# PT100.net
KiCad netlist of a schematic drawn in Altium Designer
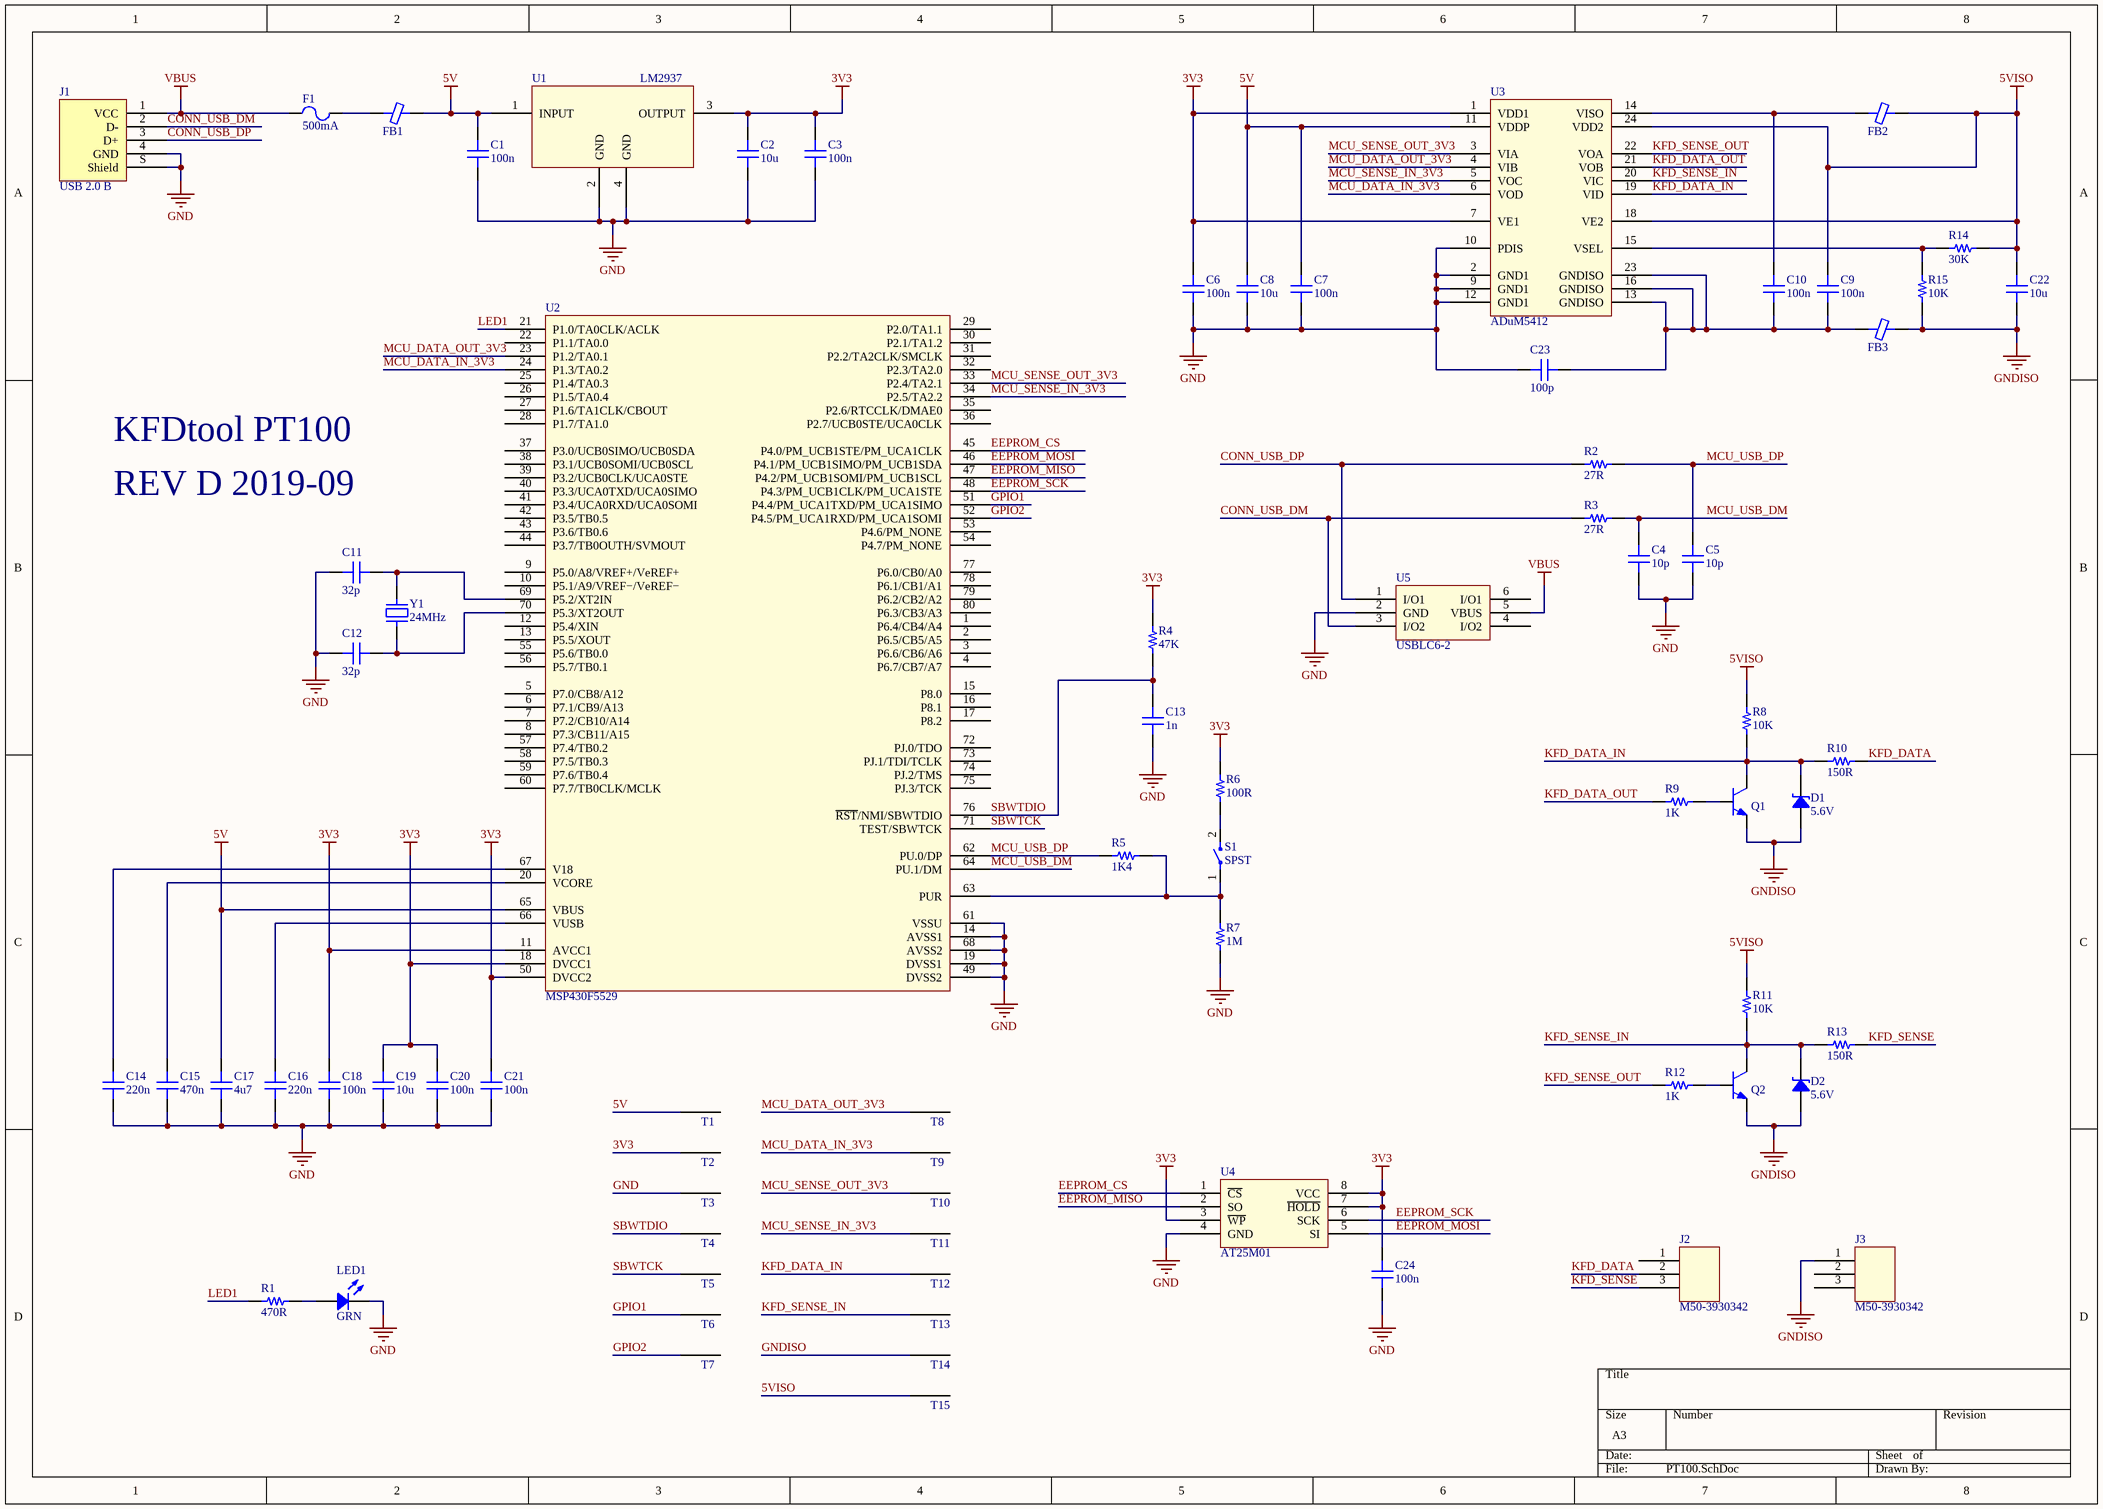
[diagram p0: PT100.SchDoc]

(export (version "E")
  (design (tool "Eeschema 10.0.6"))
  (components
    (comp (ref "C1")
      (value "100n")
      (footprint "CAP 0603")
      (libsource (lib "KFDtool Schematic Library") (part "Capacitor"))
    )
    (comp (ref "C2")
      (value "10u")
      (footprint "CAP 0603")
      (libsource (lib "KFDtool Schematic Library") (part "Capacitor"))
    )
    (comp (ref "C3")
      (value "100n")
      (footprint "CAP 0603")
      (libsource (lib "KFDtool Schematic Library") (part "Capacitor"))
    )
    (comp (ref "C4")
      (value "10p")
      (footprint "CAP 0603")
      (libsource (lib "KFDtool Schematic Library") (part "Capacitor"))
    )
    (comp (ref "C5")
      (value "10p")
      (footprint "CAP 0603")
      (libsource (lib "KFDtool Schematic Library") (part "Capacitor"))
    )
    (comp (ref "C6")
      (value "100n")
      (footprint "CAP 0603")
      (libsource (lib "KFDtool Schematic Library") (part "Capacitor"))
    )
    (comp (ref "C7")
      (value "100n")
      (footprint "CAP 0603")
      (libsource (lib "KFDtool Schematic Library") (part "Capacitor"))
    )
    (comp (ref "C8")
      (value "10u")
      (footprint "CAP 0603")
      (libsource (lib "KFDtool Schematic Library") (part "Capacitor"))
    )
    (comp (ref "C9")
      (value "100n")
      (footprint "CAP 0603")
      (libsource (lib "KFDtool Schematic Library") (part "Capacitor"))
    )
    (comp (ref "C10")
      (value "100n")
      (footprint "CAP 0603")
      (libsource (lib "KFDtool Schematic Library") (part "Capacitor"))
    )
    (comp (ref "C11")
      (value "32p")
      (footprint "CAP 0603")
      (libsource (lib "KFDtool Schematic Library") (part "Capacitor"))
    )
    (comp (ref "C12")
      (value "32p")
      (footprint "CAP 0603")
      (libsource (lib "KFDtool Schematic Library") (part "Capacitor"))
    )
    (comp (ref "C13")
      (value "1n")
      (footprint "CAP 0603")
      (libsource (lib "KFDtool Schematic Library") (part "Capacitor"))
    )
    (comp (ref "C14")
      (value "220n")
      (footprint "CAP 0603")
      (libsource (lib "KFDtool Schematic Library") (part "Capacitor"))
    )
    (comp (ref "C15")
      (value "470n")
      (footprint "CAP 0603")
      (libsource (lib "KFDtool Schematic Library") (part "Capacitor"))
    )
    (comp (ref "C16")
      (value "220n")
      (footprint "CAP 0603")
      (libsource (lib "KFDtool Schematic Library") (part "Capacitor"))
    )
    (comp (ref "C17")
      (value "4u7")
      (footprint "CAP 0603")
      (libsource (lib "KFDtool Schematic Library") (part "Capacitor"))
    )
    (comp (ref "C18")
      (value "100n")
      (footprint "CAP 0603")
      (libsource (lib "KFDtool Schematic Library") (part "Capacitor"))
    )
    (comp (ref "C19")
      (value "10u")
      (footprint "CAP 0603")
      (libsource (lib "KFDtool Schematic Library") (part "Capacitor"))
    )
    (comp (ref "C20")
      (value "100n")
      (footprint "CAP 0603")
      (libsource (lib "KFDtool Schematic Library") (part "Capacitor"))
    )
    (comp (ref "C21")
      (value "100n")
      (footprint "CAP 0603")
      (libsource (lib "KFDtool Schematic Library") (part "Capacitor"))
    )
    (comp (ref "C22")
      (value "10u")
      (footprint "CAP 0603")
      (libsource (lib "KFDtool Schematic Library") (part "Capacitor"))
    )
    (comp (ref "C23")
      (value "100p")
      (footprint "CAP 1812")
      (libsource (lib "KFDtool Schematic Library") (part "Capacitor"))
    )
    (comp (ref "C24")
      (value "100n")
      (footprint "CAP 0603")
      (libsource (lib "KFDtool Schematic Library") (part "Capacitor"))
    )
    (comp (ref "D1")
      (value "5.6V")
      (footprint "ON SEMI SOT-23-3")
      (libsource (lib "KFDtool Schematic Library") (part "Zener Diode"))
    )
    (comp (ref "D2")
      (value "5.6V")
      (footprint "ON SEMI SOT-23-3")
      (libsource (lib "KFDtool Schematic Library") (part "Zener Diode"))
    )
    (comp (ref "F1")
      (value "500mA")
      (footprint "PTC 2920")
      (libsource (lib "KFDtool Schematic Library") (part "PTC"))
    )
    (comp (ref "FB1")
      (value "Ferrite Chip")
      (footprint "CAP 0603")
      (libsource (lib "KFDtool Schematic Library") (part "Ferrite Chip"))
    )
    (comp (ref "FB2")
      (value "Ferrite Chip")
      (footprint "CAP 0603")
      (libsource (lib "KFDtool Schematic Library") (part "Ferrite Chip"))
    )
    (comp (ref "FB3")
      (value "Ferrite Chip")
      (footprint "CAP 0603")
      (libsource (lib "KFDtool Schematic Library") (part "Ferrite Chip"))
    )
    (comp (ref "J1")
      (value "USB 2.0 B")
      (footprint "FCI 61729-1011BLF")
      (libsource (lib "KFDtool Schematic Library") (part "FCI 61729-1011BLF"))
    )
    (comp (ref "J2")
      (value "M50-3930342")
      (footprint "HWN M50-3930342")
      (libsource (lib "KFDtool Schematic Library") (part "HWN M50-3930342"))
    )
    (comp (ref "J3")
      (value "M50-3930342")
      (footprint "HWN M50-3930342")
      (libsource (lib "KFDtool Schematic Library") (part "HWN M50-3930342"))
    )
    (comp (ref "LED1")
      (value "GRN")
      (footprint "KBRT WP934CB/GD")
      (libsource (lib "KFDtool Schematic Library") (part "LED"))
    )
    (comp (ref "Q1")
      (value "NPN Transistor")
      (footprint "ON SEMI SOT-23-3")
      (libsource (lib "KFDtool Schematic Library") (part "NPN Transistor"))
    )
    (comp (ref "Q2")
      (value "NPN Transistor")
      (footprint "ON SEMI SOT-23-3")
      (libsource (lib "KFDtool Schematic Library") (part "NPN Transistor"))
    )
    (comp (ref "R1")
      (value "470R")
      (footprint "RES 0603")
      (libsource (lib "KFDtool Schematic Library") (part "Resistor"))
    )
    (comp (ref "R2")
      (value "27R")
      (footprint "RES 0603")
      (libsource (lib "KFDtool Schematic Library") (part "Resistor"))
    )
    (comp (ref "R3")
      (value "27R")
      (footprint "RES 0603")
      (libsource (lib "KFDtool Schematic Library") (part "Resistor"))
    )
    (comp (ref "R4")
      (value "47K")
      (footprint "RES 0603")
      (libsource (lib "KFDtool Schematic Library") (part "Resistor"))
    )
    (comp (ref "R5")
      (value "1K4")
      (footprint "RES 0603")
      (libsource (lib "KFDtool Schematic Library") (part "Resistor"))
    )
    (comp (ref "R6")
      (value "100R")
      (footprint "RES 0603")
      (libsource (lib "KFDtool Schematic Library") (part "Resistor"))
    )
    (comp (ref "R7")
      (value "1M")
      (footprint "RES 0603")
      (libsource (lib "KFDtool Schematic Library") (part "Resistor"))
    )
    (comp (ref "R8")
      (value "10K")
      (footprint "RES 0603")
      (libsource (lib "KFDtool Schematic Library") (part "Resistor"))
    )
    (comp (ref "R9")
      (value "1K")
      (footprint "RES 0603")
      (libsource (lib "KFDtool Schematic Library") (part "Resistor"))
    )
    (comp (ref "R10")
      (value "150R")
      (footprint "RES 0603")
      (libsource (lib "KFDtool Schematic Library") (part "Resistor"))
    )
    (comp (ref "R11")
      (value "10K")
      (footprint "RES 0603")
      (libsource (lib "KFDtool Schematic Library") (part "Resistor"))
    )
    (comp (ref "R12")
      (value "1K")
      (footprint "RES 0603")
      (libsource (lib "KFDtool Schematic Library") (part "Resistor"))
    )
    (comp (ref "R13")
      (value "150R")
      (footprint "RES 0603")
      (libsource (lib "KFDtool Schematic Library") (part "Resistor"))
    )
    (comp (ref "R14")
      (value "30K")
      (footprint "RES 0603")
      (libsource (lib "KFDtool Schematic Library") (part "Resistor"))
    )
    (comp (ref "R15")
      (value "10K")
      (footprint "RES 0603")
      (libsource (lib "KFDtool Schematic Library") (part "Resistor"))
    )
    (comp (ref "S1")
      (value "SPST")
      (footprint "ESWI TL3340AF160QG")
      (libsource (lib "KFDtool Schematic Library") (part "SPST Switch"))
    )
    (comp (ref "T1")
      (value "Test Point")
      (footprint "TEST POINT")
      (libsource (lib "KFDtool Schematic Library") (part "Test Point"))
    )
    (comp (ref "T2")
      (value "Test Point")
      (footprint "TEST POINT")
      (libsource (lib "KFDtool Schematic Library") (part "Test Point"))
    )
    (comp (ref "T3")
      (value "Test Point")
      (footprint "TEST POINT")
      (libsource (lib "KFDtool Schematic Library") (part "Test Point"))
    )
    (comp (ref "T4")
      (value "Test Point")
      (footprint "TEST POINT")
      (libsource (lib "KFDtool Schematic Library") (part "Test Point"))
    )
    (comp (ref "T5")
      (value "Test Point")
      (footprint "TEST POINT")
      (libsource (lib "KFDtool Schematic Library") (part "Test Point"))
    )
    (comp (ref "T6")
      (value "Test Point")
      (footprint "TEST POINT")
      (libsource (lib "KFDtool Schematic Library") (part "Test Point"))
    )
    (comp (ref "T7")
      (value "Test Point")
      (footprint "TEST POINT")
      (libsource (lib "KFDtool Schematic Library") (part "Test Point"))
    )
    (comp (ref "T8")
      (value "Test Point")
      (footprint "TEST POINT")
      (libsource (lib "KFDtool Schematic Library") (part "Test Point"))
    )
    (comp (ref "T9")
      (value "Test Point")
      (footprint "TEST POINT")
      (libsource (lib "KFDtool Schematic Library") (part "Test Point"))
    )
    (comp (ref "T10")
      (value "Test Point")
      (footprint "TEST POINT")
      (libsource (lib "KFDtool Schematic Library") (part "Test Point"))
    )
    (comp (ref "T11")
      (value "Test Point")
      (footprint "TEST POINT")
      (libsource (lib "KFDtool Schematic Library") (part "Test Point"))
    )
    (comp (ref "T12")
      (value "Test Point")
      (footprint "TEST POINT")
      (libsource (lib "KFDtool Schematic Library") (part "Test Point"))
    )
    (comp (ref "T13")
      (value "Test Point")
      (footprint "TEST POINT")
      (libsource (lib "KFDtool Schematic Library") (part "Test Point"))
    )
    (comp (ref "T14")
      (value "Test Point")
      (footprint "TEST POINT")
      (libsource (lib "KFDtool Schematic Library") (part "Test Point"))
    )
    (comp (ref "T15")
      (value "Test Point")
      (footprint "TEST POINT")
      (libsource (lib "KFDtool Schematic Library") (part "Test Point"))
    )
    (comp (ref "U1")
      (value "LM2937")
      (footprint "TI LM2937IMP-3.3/NOPB")
      (libsource (lib "KFDtool Schematic Library") (part "TI LM2937"))
    )
    (comp (ref "U2")
      (value "MSP430F5529")
      (footprint "TI MSP430F5529IPNR")
      (libsource (lib "KFDtool Schematic Library") (part "TI MSP430F5529"))
    )
    (comp (ref "U3")
      (value "ADuM5412")
      (footprint "AD RS-24")
      (libsource (lib "KFDtool Schematic Library") (part "AD ADuM5412"))
    )
    (comp (ref "U4")
      (value "AT25M01")
      (footprint "ATML 8S1")
      (libsource (lib "KFDtool Schematic Library") (part "ATML AT25M01"))
    )
    (comp (ref "U5")
      (value "USBLC6-2")
      (footprint "ST SOT23-6L")
      (libsource (lib "KFDtool Schematic Library") (part "ST USBLC6-2"))
    )
    (comp (ref "Y1")
      (value "24MHz")
      (footprint "ABRA ABLS2")
      (libsource (lib "KFDtool Schematic Library") (part "Crystal"))
    )
  )
  (nets
    (net (code "1") (name "/CONN_USB_DM") (class "Default")
      (node (ref "J1") (pin "2") (pinfunction "D-_2") (pintype "passive"))
      (node (ref "R3") (pin "1") (pinfunction "1_1") (pintype "passive"))
      (node (ref "U5") (pin "3") (pinfunction "I/O2_3") (pintype "passive"))
    )
    (net (code "2") (name "/CONN_USB_DP") (class "Default")
      (node (ref "J1") (pin "3") (pinfunction "D+_3") (pintype "passive"))
      (node (ref "R2") (pin "1") (pinfunction "1_1") (pintype "passive"))
      (node (ref "U5") (pin "1") (pinfunction "I/O1_1") (pintype "passive"))
    )
    (net (code "3") (name "/EEPROM_CS") (class "Default")
      (node (ref "U2") (pin "45") (pinfunction "P4.0/PM_UCB1STE/PM_UCA1CLK_45") (pintype "passive"))
      (node (ref "U4") (pin "1") (pinfunction "~{CS}_1") (pintype "passive"))
    )
    (net (code "4") (name "/EEPROM_MISO") (class "Default")
      (node (ref "U2") (pin "47") (pinfunction "P4.2/PM_UCB1SOMI/PM_UCB1SCL_47") (pintype "passive"))
      (node (ref "U4") (pin "2") (pinfunction "SO_2") (pintype "passive"))
    )
    (net (code "5") (name "/EEPROM_MOSI") (class "Default")
      (node (ref "U2") (pin "46") (pinfunction "P4.1/PM_UCB1SIMO/PM_UCB1SDA_46") (pintype "passive"))
      (node (ref "U4") (pin "5") (pinfunction "SI_5") (pintype "passive"))
    )
    (net (code "6") (name "/EEPROM_SCK") (class "Default")
      (node (ref "U2") (pin "48") (pinfunction "P4.3/PM_UCB1CLK/PM_UCA1STE_48") (pintype "passive"))
      (node (ref "U4") (pin "6") (pinfunction "SCK_6") (pintype "passive"))
    )
    (net (code "7") (name "/GPIO1") (class "Default")
      (node (ref "T6") (pin "1") (pinfunction "1_1") (pintype "passive"))
      (node (ref "U2") (pin "51") (pinfunction "P4.4/PM_UCA1TXD/PM_UCA1SIMO_51") (pintype "passive"))
    )
    (net (code "8") (name "/GPIO2") (class "Default")
      (node (ref "T7") (pin "1") (pinfunction "1_1") (pintype "passive"))
      (node (ref "U2") (pin "52") (pinfunction "P4.5/PM_UCA1RXD/PM_UCA1SOMI_52") (pintype "passive"))
    )
    (net (code "9") (name "/KFD_DATA") (class "Default")
      (node (ref "J2") (pin "2") (pinfunction "2_2") (pintype "passive"))
      (node (ref "R10") (pin "2") (pinfunction "2_2") (pintype "passive"))
    )
    (net (code "10") (name "/KFD_DATA_IN") (class "Default")
      (node (ref "D1") (pin "C") (pinfunction "C_C") (pintype "passive"))
      (node (ref "Q1") (pin "C") (pinfunction "C_C") (pintype "passive"))
      (node (ref "R10") (pin "1") (pinfunction "1_1") (pintype "passive"))
      (node (ref "R8") (pin "1") (pinfunction "1_1") (pintype "passive"))
      (node (ref "T12") (pin "1") (pinfunction "1_1") (pintype "passive"))
      (node (ref "U3") (pin "19") (pinfunction "VID_19") (pintype "passive"))
    )
    (net (code "11") (name "/KFD_DATA_OUT") (class "Default")
      (node (ref "R9") (pin "1") (pinfunction "1_1") (pintype "passive"))
      (node (ref "U3") (pin "21") (pinfunction "VOB_21") (pintype "passive"))
    )
    (net (code "12") (name "/KFD_SENSE") (class "Default")
      (node (ref "J2") (pin "3") (pinfunction "3_3") (pintype "passive"))
      (node (ref "R13") (pin "2") (pinfunction "2_2") (pintype "passive"))
    )
    (net (code "13") (name "/KFD_SENSE_IN") (class "Default")
      (node (ref "D2") (pin "C") (pinfunction "C_C") (pintype "passive"))
      (node (ref "Q2") (pin "C") (pinfunction "C_C") (pintype "passive"))
      (node (ref "R11") (pin "1") (pinfunction "1_1") (pintype "passive"))
      (node (ref "R13") (pin "1") (pinfunction "1_1") (pintype "passive"))
      (node (ref "T13") (pin "1") (pinfunction "1_1") (pintype "passive"))
      (node (ref "U3") (pin "20") (pinfunction "VIC_20") (pintype "passive"))
    )
    (net (code "14") (name "/KFD_SENSE_OUT") (class "Default")
      (node (ref "R12") (pin "1") (pinfunction "1_1") (pintype "passive"))
      (node (ref "U3") (pin "22") (pinfunction "VOA_22") (pintype "passive"))
    )
    (net (code "15") (name "/LED1") (class "Default")
      (node (ref "R1") (pin "1") (pinfunction "1_1") (pintype "passive"))
      (node (ref "U2") (pin "21") (pinfunction "P1.0/TA0CLK/ACLK_21") (pintype "passive"))
    )
    (net (code "16") (name "/MCU_DATA_IN_3V3") (class "Default")
      (node (ref "T9") (pin "1") (pinfunction "1_1") (pintype "passive"))
      (node (ref "U2") (pin "24") (pinfunction "P1.3/TA0.2_24") (pintype "passive"))
      (node (ref "U3") (pin "6") (pinfunction "VOD_6") (pintype "passive"))
    )
    (net (code "17") (name "/MCU_DATA_OUT_3V3") (class "Default")
      (node (ref "T8") (pin "1") (pinfunction "1_1") (pintype "passive"))
      (node (ref "U2") (pin "23") (pinfunction "P1.2/TA0.1_23") (pintype "passive"))
      (node (ref "U3") (pin "4") (pinfunction "VIB_4") (pintype "passive"))
    )
    (net (code "18") (name "/MCU_SENSE_IN_3V3") (class "Default")
      (node (ref "T11") (pin "1") (pinfunction "1_1") (pintype "passive"))
      (node (ref "U2") (pin "34") (pinfunction "P2.5/TA2.2_34") (pintype "passive"))
      (node (ref "U3") (pin "5") (pinfunction "VOC_5") (pintype "passive"))
    )
    (net (code "19") (name "/MCU_SENSE_OUT_3V3") (class "Default")
      (node (ref "T10") (pin "1") (pinfunction "1_1") (pintype "passive"))
      (node (ref "U2") (pin "33") (pinfunction "P2.4/TA2.1_33") (pintype "passive"))
      (node (ref "U3") (pin "3") (pinfunction "VIA_3") (pintype "passive"))
    )
    (net (code "20") (name "/MCU_USB_DM") (class "Default")
      (node (ref "C4") (pin "2") (pinfunction "2_2") (pintype "passive"))
      (node (ref "R3") (pin "2") (pinfunction "2_2") (pintype "passive"))
      (node (ref "U2") (pin "64") (pinfunction "PU.1/DM_64") (pintype "passive"))
    )
    (net (code "21") (name "/MCU_USB_DP") (class "Default")
      (node (ref "C5") (pin "2") (pinfunction "2_2") (pintype "passive"))
      (node (ref "R2") (pin "2") (pinfunction "2_2") (pintype "passive"))
      (node (ref "R5") (pin "1") (pinfunction "1_1") (pintype "passive"))
      (node (ref "U2") (pin "62") (pinfunction "PU.0/DP_62") (pintype "passive"))
    )
    (net (code "22") (name "/SBWTCK") (class "Default")
      (node (ref "T5") (pin "1") (pinfunction "1_1") (pintype "passive"))
      (node (ref "U2") (pin "71") (pinfunction "TEST/SBWTCK_71") (pintype "passive"))
    )
    (net (code "23") (name "/SBWTDIO") (class "Default")
      (node (ref "C13") (pin "2") (pinfunction "2_2") (pintype "passive"))
      (node (ref "R4") (pin "1") (pinfunction "1_1") (pintype "passive"))
      (node (ref "T4") (pin "1") (pinfunction "1_1") (pintype "passive"))
      (node (ref "U2") (pin "76") (pinfunction "~{RST}/NMI/SBWTDIO_76") (pintype "passive"))
    )
    (net (code "24") (name "3V3") (class "Default")
      (node (ref "C18") (pin "2") (pinfunction "2_2") (pintype "passive"))
      (node (ref "C19") (pin "2") (pinfunction "2_2") (pintype "passive"))
      (node (ref "C2") (pin "2") (pinfunction "2_2") (pintype "passive"))
      (node (ref "C20") (pin "2") (pinfunction "2_2") (pintype "passive"))
      (node (ref "C21") (pin "2") (pinfunction "2_2") (pintype "passive"))
      (node (ref "C24") (pin "2") (pinfunction "2_2") (pintype "passive"))
      (node (ref "C3") (pin "2") (pinfunction "2_2") (pintype "passive"))
      (node (ref "C6") (pin "2") (pinfunction "2_2") (pintype "passive"))
      (node (ref "R4") (pin "2") (pinfunction "2_2") (pintype "passive"))
      (node (ref "R6") (pin "2") (pinfunction "2_2") (pintype "passive"))
      (node (ref "T2") (pin "1") (pinfunction "1_1") (pintype "passive"))
      (node (ref "U1") (pin "3") (pinfunction "OUTPUT_3") (pintype "passive"))
      (node (ref "U2") (pin "11") (pinfunction "AVCC1_11") (pintype "passive"))
      (node (ref "U2") (pin "18") (pinfunction "DVCC1_18") (pintype "passive"))
      (node (ref "U2") (pin "50") (pinfunction "DVCC2_50") (pintype "passive"))
      (node (ref "U3") (pin "1") (pinfunction "VDD1_1") (pintype "passive"))
      (node (ref "U3") (pin "7") (pinfunction "VE1_7") (pintype "passive"))
      (node (ref "U4") (pin "3") (pinfunction "~{WP}_3") (pintype "passive"))
      (node (ref "U4") (pin "7") (pinfunction "~{HOLD}_7") (pintype "passive"))
      (node (ref "U4") (pin "8") (pinfunction "VCC_8") (pintype "passive"))
    )
    (net (code "25") (name "5V") (class "Default")
      (node (ref "C1") (pin "2") (pinfunction "2_2") (pintype "passive"))
      (node (ref "C17") (pin "2") (pinfunction "2_2") (pintype "passive"))
      (node (ref "C7") (pin "2") (pinfunction "2_2") (pintype "passive"))
      (node (ref "C8") (pin "2") (pinfunction "2_2") (pintype "passive"))
      (node (ref "FB1") (pin "2") (pinfunction "2_2") (pintype "passive"))
      (node (ref "T1") (pin "1") (pinfunction "1_1") (pintype "passive"))
      (node (ref "U1") (pin "1") (pinfunction "INPUT_1") (pintype "passive"))
      (node (ref "U2") (pin "65") (pinfunction "VBUS_65") (pintype "passive"))
      (node (ref "U3") (pin "11") (pinfunction "VDDP_11") (pintype "passive"))
    )
    (net (code "26") (name "5VISO") (class "Default")
      (node (ref "C22") (pin "2") (pinfunction "2_2") (pintype "passive"))
      (node (ref "C9") (pin "2") (pinfunction "2_2") (pintype "passive"))
      (node (ref "FB2") (pin "2") (pinfunction "2_2") (pintype "passive"))
      (node (ref "R11") (pin "2") (pinfunction "2_2") (pintype "passive"))
      (node (ref "R14") (pin "1") (pinfunction "1_1") (pintype "passive"))
      (node (ref "R8") (pin "2") (pinfunction "2_2") (pintype "passive"))
      (node (ref "T15") (pin "1") (pinfunction "1_1") (pintype "passive"))
      (node (ref "U3") (pin "18") (pinfunction "VE2_18") (pintype "passive"))
      (node (ref "U3") (pin "24") (pinfunction "VDD2_24") (pintype "passive"))
    )
    (net (code "27") (name "GND") (class "Default")
      (node (ref "C1") (pin "1") (pinfunction "1_1") (pintype "passive"))
      (node (ref "C11") (pin "1") (pinfunction "1_1") (pintype "passive"))
      (node (ref "C12") (pin "1") (pinfunction "1_1") (pintype "passive"))
      (node (ref "C13") (pin "1") (pinfunction "1_1") (pintype "passive"))
      (node (ref "C14") (pin "1") (pinfunction "1_1") (pintype "passive"))
      (node (ref "C15") (pin "1") (pinfunction "1_1") (pintype "passive"))
      (node (ref "C16") (pin "1") (pinfunction "1_1") (pintype "passive"))
      (node (ref "C17") (pin "1") (pinfunction "1_1") (pintype "passive"))
      (node (ref "C18") (pin "1") (pinfunction "1_1") (pintype "passive"))
      (node (ref "C19") (pin "1") (pinfunction "1_1") (pintype "passive"))
      (node (ref "C2") (pin "1") (pinfunction "1_1") (pintype "passive"))
      (node (ref "C20") (pin "1") (pinfunction "1_1") (pintype "passive"))
      (node (ref "C21") (pin "1") (pinfunction "1_1") (pintype "passive"))
      (node (ref "C23") (pin "1") (pinfunction "1_1") (pintype "passive"))
      (node (ref "C24") (pin "1") (pinfunction "1_1") (pintype "passive"))
      (node (ref "C3") (pin "1") (pinfunction "1_1") (pintype "passive"))
      (node (ref "C4") (pin "1") (pinfunction "1_1") (pintype "passive"))
      (node (ref "C5") (pin "1") (pinfunction "1_1") (pintype "passive"))
      (node (ref "C6") (pin "1") (pinfunction "1_1") (pintype "passive"))
      (node (ref "C7") (pin "1") (pinfunction "1_1") (pintype "passive"))
      (node (ref "C8") (pin "1") (pinfunction "1_1") (pintype "passive"))
      (node (ref "J1") (pin "4") (pinfunction "GND_4") (pintype "passive"))
      (node (ref "J1") (pin "S") (pinfunction "Shield_S") (pintype "passive"))
      (node (ref "LED1") (pin "2") (pinfunction "2_2") (pintype "passive"))
      (node (ref "R7") (pin "1") (pinfunction "1_1") (pintype "passive"))
      (node (ref "T3") (pin "1") (pinfunction "1_1") (pintype "passive"))
      (node (ref "U1") (pin "2") (pinfunction "GND_2") (pintype "passive"))
      (node (ref "U1") (pin "4") (pinfunction "GND_4") (pintype "passive"))
      (node (ref "U2") (pin "14") (pinfunction "AVSS1_14") (pintype "passive"))
      (node (ref "U2") (pin "19") (pinfunction "DVSS1_19") (pintype "passive"))
      (node (ref "U2") (pin "49") (pinfunction "DVSS2_49") (pintype "passive"))
      (node (ref "U2") (pin "61") (pinfunction "VSSU_61") (pintype "passive"))
      (node (ref "U2") (pin "68") (pinfunction "AVSS2_68") (pintype "passive"))
      (node (ref "U3") (pin "10") (pinfunction "PDIS_10") (pintype "passive"))
      (node (ref "U3") (pin "12") (pinfunction "GND1_12") (pintype "passive"))
      (node (ref "U3") (pin "2") (pinfunction "GND1_2") (pintype "passive"))
      (node (ref "U3") (pin "9") (pinfunction "GND1_9") (pintype "passive"))
      (node (ref "U4") (pin "4") (pinfunction "GND_4") (pintype "passive"))
      (node (ref "U5") (pin "2") (pinfunction "GND_2") (pintype "passive"))
    )
    (net (code "28") (name "GNDISO") (class "Default")
      (node (ref "C22") (pin "1") (pinfunction "1_1") (pintype "passive"))
      (node (ref "D1") (pin "A") (pinfunction "A_A") (pintype "passive"))
      (node (ref "D2") (pin "A") (pinfunction "A_A") (pintype "passive"))
      (node (ref "FB3") (pin "2") (pinfunction "2_2") (pintype "passive"))
      (node (ref "J3") (pin "1") (pinfunction "1_1") (pintype "passive"))
      (node (ref "Q1") (pin "E") (pinfunction "E_E") (pintype "passive"))
      (node (ref "Q2") (pin "E") (pinfunction "E_E") (pintype "passive"))
      (node (ref "R15") (pin "1") (pinfunction "1_1") (pintype "passive"))
      (node (ref "T14") (pin "1") (pinfunction "1_1") (pintype "passive"))
    )
    (net (code "29") (name "Net-(C10-Pad1)") (class "Default")
      (node (ref "C10") (pin "1") (pinfunction "1_1") (pintype "passive"))
      (node (ref "C23") (pin "2") (pinfunction "2_2") (pintype "passive"))
      (node (ref "C9") (pin "1") (pinfunction "1_1") (pintype "passive"))
      (node (ref "FB3") (pin "1") (pinfunction "1_1") (pintype "passive"))
      (node (ref "U3") (pin "13") (pinfunction "GNDISO_13") (pintype "passive"))
      (node (ref "U3") (pin "16") (pinfunction "GNDISO_16") (pintype "passive"))
      (node (ref "U3") (pin "23") (pinfunction "GNDISO_23") (pintype "passive"))
    )
    (net (code "30") (name "Net-(F1-Pad2)") (class "Default")
      (node (ref "F1") (pin "2") (pinfunction "2_2") (pintype "passive"))
      (node (ref "FB1") (pin "1") (pinfunction "1_1") (pintype "passive"))
    )
    (net (code "31") (name "Net-(LED1-Pad1)") (class "Default")
      (node (ref "LED1") (pin "1") (pinfunction "1_1") (pintype "passive"))
      (node (ref "R1") (pin "2") (pinfunction "2_2") (pintype "passive"))
    )
    (net (code "32") (name "Net-(Q1-PadB)") (class "Default")
      (node (ref "Q1") (pin "B") (pinfunction "B_B") (pintype "passive"))
      (node (ref "R9") (pin "2") (pinfunction "2_2") (pintype "passive"))
    )
    (net (code "33") (name "Net-(Q2-PadB)") (class "Default")
      (node (ref "Q2") (pin "B") (pinfunction "B_B") (pintype "passive"))
      (node (ref "R12") (pin "2") (pinfunction "2_2") (pintype "passive"))
    )
    (net (code "34") (name "Net-(R6-Pad1)") (class "Default")
      (node (ref "R6") (pin "1") (pinfunction "1_1") (pintype "passive"))
      (node (ref "S1") (pin "2") (pinfunction "2_2") (pintype "passive"))
    )
    (net (code "35") (name "Net-(U2-P5.2{slash}XT2IN)") (class "Default")
      (node (ref "C11") (pin "2") (pinfunction "2_2") (pintype "passive"))
      (node (ref "U2") (pin "69") (pinfunction "P5.2/XT2IN_69") (pintype "passive"))
      (node (ref "Y1") (pin "2") (pinfunction "2_2") (pintype "passive"))
    )
    (net (code "36") (name "Net-(U2-P5.3{slash}XT2OUT)") (class "Default")
      (node (ref "C12") (pin "2") (pinfunction "2_2") (pintype "passive"))
      (node (ref "U2") (pin "70") (pinfunction "P5.3/XT2OUT_70") (pintype "passive"))
      (node (ref "Y1") (pin "1") (pinfunction "1_1") (pintype "passive"))
    )
    (net (code "37") (name "Net-(U2-PUR)") (class "Default")
      (node (ref "R5") (pin "2") (pinfunction "2_2") (pintype "passive"))
      (node (ref "R7") (pin "2") (pinfunction "2_2") (pintype "passive"))
      (node (ref "S1") (pin "1") (pinfunction "1_1") (pintype "passive"))
      (node (ref "U2") (pin "63") (pinfunction "PUR_63") (pintype "passive"))
    )
    (net (code "38") (name "Net-(U2-V18)") (class "Default")
      (node (ref "C14") (pin "2") (pinfunction "2_2") (pintype "passive"))
      (node (ref "U2") (pin "67") (pinfunction "V18_67") (pintype "passive"))
    )
    (net (code "39") (name "Net-(U2-VCORE)") (class "Default")
      (node (ref "C15") (pin "2") (pinfunction "2_2") (pintype "passive"))
      (node (ref "U2") (pin "20") (pinfunction "VCORE_20") (pintype "passive"))
    )
    (net (code "40") (name "Net-(U2-VUSB)") (class "Default")
      (node (ref "C16") (pin "2") (pinfunction "2_2") (pintype "passive"))
      (node (ref "U2") (pin "66") (pinfunction "VUSB_66") (pintype "passive"))
    )
    (net (code "41") (name "Net-(U3-VISO)") (class "Default")
      (node (ref "C10") (pin "2") (pinfunction "2_2") (pintype "passive"))
      (node (ref "FB2") (pin "1") (pinfunction "1_1") (pintype "passive"))
      (node (ref "U3") (pin "14") (pinfunction "VISO_14") (pintype "passive"))
    )
    (net (code "42") (name "Net-(U3-VSEL)") (class "Default")
      (node (ref "R14") (pin "2") (pinfunction "2_2") (pintype "passive"))
      (node (ref "R15") (pin "2") (pinfunction "2_2") (pintype "passive"))
      (node (ref "U3") (pin "15") (pinfunction "VSEL_15") (pintype "passive"))
    )
    (net (code "43") (name "VBUS") (class "Default")
      (node (ref "F1") (pin "1") (pinfunction "1_1") (pintype "passive"))
      (node (ref "J1") (pin "1") (pinfunction "VCC_1") (pintype "passive"))
      (node (ref "U5") (pin "5") (pinfunction "VBUS_5") (pintype "passive"))
    )
    (net (code "44") (name "unconnected-(J2-Pad1)") (class "Default")
      (node (ref "J2") (pin "1") (pinfunction "1_1") (pintype "passive"))
    )
    (net (code "45") (name "unconnected-(J3-Pad2)") (class "Default")
      (node (ref "J3") (pin "2") (pinfunction "2_2") (pintype "passive"))
    )
    (net (code "46") (name "unconnected-(J3-Pad3)") (class "Default")
      (node (ref "J3") (pin "3") (pinfunction "3_3") (pintype "passive"))
    )
    (net (code "47") (name "unconnected-(U2-P1.1{slash}TA0.0-Pad22)") (class "Default")
      (node (ref "U2") (pin "22") (pinfunction "P1.1/TA0.0_22") (pintype "passive"))
    )
    (net (code "48") (name "unconnected-(U2-P1.4{slash}TA0.3-Pad25)") (class "Default")
      (node (ref "U2") (pin "25") (pinfunction "P1.4/TA0.3_25") (pintype "passive"))
    )
    (net (code "49") (name "unconnected-(U2-P1.5{slash}TA0.4-Pad26)") (class "Default")
      (node (ref "U2") (pin "26") (pinfunction "P1.5/TA0.4_26") (pintype "passive"))
    )
    (net (code "50") (name "unconnected-(U2-P1.6{slash}TA1CLK{slash}CBOUT-Pad27)") (class "Default")
      (node (ref "U2") (pin "27") (pinfunction "P1.6/TA1CLK/CBOUT_27") (pintype "passive"))
    )
    (net (code "51") (name "unconnected-(U2-P1.7{slash}TA1.0-Pad28)") (class "Default")
      (node (ref "U2") (pin "28") (pinfunction "P1.7/TA1.0_28") (pintype "passive"))
    )
    (net (code "52") (name "unconnected-(U2-P2.0{slash}TA1.1-Pad29)") (class "Default")
      (node (ref "U2") (pin "29") (pinfunction "P2.0/TA1.1_29") (pintype "passive"))
    )
    (net (code "53") (name "unconnected-(U2-P2.1{slash}TA1.2-Pad30)") (class "Default")
      (node (ref "U2") (pin "30") (pinfunction "P2.1/TA1.2_30") (pintype "passive"))
    )
    (net (code "54") (name "unconnected-(U2-P2.2{slash}TA2CLK{slash}SMCLK-Pad31)") (class "Default")
      (node (ref "U2") (pin "31") (pinfunction "P2.2/TA2CLK/SMCLK_31") (pintype "passive"))
    )
    (net (code "55") (name "unconnected-(U2-P2.3{slash}TA2.0-Pad32)") (class "Default")
      (node (ref "U2") (pin "32") (pinfunction "P2.3/TA2.0_32") (pintype "passive"))
    )
    (net (code "56") (name "unconnected-(U2-P2.6{slash}RTCCLK{slash}DMAE0-Pad35)") (class "Default")
      (node (ref "U2") (pin "35") (pinfunction "P2.6/RTCCLK/DMAE0_35") (pintype "passive"))
    )
    (net (code "57") (name "unconnected-(U2-P2.7{slash}UCB0STE{slash}UCA0CLK-Pad36)") (class "Default")
      (node (ref "U2") (pin "36") (pinfunction "P2.7/UCB0STE/UCA0CLK_36") (pintype "passive"))
    )
    (net (code "58") (name "unconnected-(U2-P3.0{slash}UCB0SIMO{slash}UCB0SDA-Pad37)") (class "Default")
      (node (ref "U2") (pin "37") (pinfunction "P3.0/UCB0SIMO/UCB0SDA_37") (pintype "passive"))
    )
    (net (code "59") (name "unconnected-(U2-P3.1{slash}UCB0SOMI{slash}UCB0SCL-Pad38)") (class "Default")
      (node (ref "U2") (pin "38") (pinfunction "P3.1/UCB0SOMI/UCB0SCL_38") (pintype "passive"))
    )
    (net (code "60") (name "unconnected-(U2-P3.2{slash}UCB0CLK{slash}UCA0STE-Pad39)") (class "Default")
      (node (ref "U2") (pin "39") (pinfunction "P3.2/UCB0CLK/UCA0STE_39") (pintype "passive"))
    )
    (net (code "61") (name "unconnected-(U2-P3.3{slash}UCA0TXD{slash}UCA0SIMO-Pad40)") (class "Default")
      (node (ref "U2") (pin "40") (pinfunction "P3.3/UCA0TXD/UCA0SIMO_40") (pintype "passive"))
    )
    (net (code "62") (name "unconnected-(U2-P3.4{slash}UCA0RXD{slash}UCA0SOMI-Pad41)") (class "Default")
      (node (ref "U2") (pin "41") (pinfunction "P3.4/UCA0RXD/UCA0SOMI_41") (pintype "passive"))
    )
    (net (code "63") (name "unconnected-(U2-P3.5{slash}TB0.5-Pad42)") (class "Default")
      (node (ref "U2") (pin "42") (pinfunction "P3.5/TB0.5_42") (pintype "passive"))
    )
    (net (code "64") (name "unconnected-(U2-P3.6{slash}TB0.6-Pad43)") (class "Default")
      (node (ref "U2") (pin "43") (pinfunction "P3.6/TB0.6_43") (pintype "passive"))
    )
    (net (code "65") (name "unconnected-(U2-P3.7{slash}TB0OUTH{slash}SVMOUT-Pad44)") (class "Default")
      (node (ref "U2") (pin "44") (pinfunction "P3.7/TB0OUTH/SVMOUT_44") (pintype "passive"))
    )
    (net (code "66") (name "unconnected-(U2-P4.6{slash}PM_NONE-Pad53)") (class "Default")
      (node (ref "U2") (pin "53") (pinfunction "P4.6/PM_NONE_53") (pintype "passive"))
    )
    (net (code "67") (name "unconnected-(U2-P4.7{slash}PM_NONE-Pad54)") (class "Default")
      (node (ref "U2") (pin "54") (pinfunction "P4.7/PM_NONE_54") (pintype "passive"))
    )
    (net (code "68") (name "unconnected-(U2-P5.0{slash}A8{slash}VREF+{slash}VeREF+-Pad9)") (class "Default")
      (node (ref "U2") (pin "9") (pinfunction "P5.0/A8/VREF+/VeREF+_9") (pintype "passive"))
    )
    (net (code "69") (name "unconnected-(U2-P5.1{slash}A9{slash}VREF−{slash}VeREF−-Pad10)") (class "Default")
      (node (ref "U2") (pin "10") (pinfunction "P5.1/A9/VREF−/VeREF−_10") (pintype "passive"))
    )
    (net (code "70") (name "unconnected-(U2-P5.4{slash}XIN-Pad12)") (class "Default")
      (node (ref "U2") (pin "12") (pinfunction "P5.4/XIN_12") (pintype "passive"))
    )
    (net (code "71") (name "unconnected-(U2-P5.5{slash}XOUT-Pad13)") (class "Default")
      (node (ref "U2") (pin "13") (pinfunction "P5.5/XOUT_13") (pintype "passive"))
    )
    (net (code "72") (name "unconnected-(U2-P5.6{slash}TB0.0-Pad55)") (class "Default")
      (node (ref "U2") (pin "55") (pinfunction "P5.6/TB0.0_55") (pintype "passive"))
    )
    (net (code "73") (name "unconnected-(U2-P5.7{slash}TB0.1-Pad56)") (class "Default")
      (node (ref "U2") (pin "56") (pinfunction "P5.7/TB0.1_56") (pintype "passive"))
    )
    (net (code "74") (name "unconnected-(U2-P6.0{slash}CB0{slash}A0-Pad77)") (class "Default")
      (node (ref "U2") (pin "77") (pinfunction "P6.0/CB0/A0_77") (pintype "passive"))
    )
    (net (code "75") (name "unconnected-(U2-P6.1{slash}CB1{slash}A1-Pad78)") (class "Default")
      (node (ref "U2") (pin "78") (pinfunction "P6.1/CB1/A1_78") (pintype "passive"))
    )
    (net (code "76") (name "unconnected-(U2-P6.2{slash}CB2{slash}A2-Pad79)") (class "Default")
      (node (ref "U2") (pin "79") (pinfunction "P6.2/CB2/A2_79") (pintype "passive"))
    )
    (net (code "77") (name "unconnected-(U2-P6.3{slash}CB3{slash}A3-Pad80)") (class "Default")
      (node (ref "U2") (pin "80") (pinfunction "P6.3/CB3/A3_80") (pintype "passive"))
    )
    (net (code "78") (name "unconnected-(U2-P6.4{slash}CB4{slash}A4-Pad1)") (class "Default")
      (node (ref "U2") (pin "1") (pinfunction "P6.4/CB4/A4_1") (pintype "passive"))
    )
    (net (code "79") (name "unconnected-(U2-P6.5{slash}CB5{slash}A5-Pad2)") (class "Default")
      (node (ref "U2") (pin "2") (pinfunction "P6.5/CB5/A5_2") (pintype "passive"))
    )
    (net (code "80") (name "unconnected-(U2-P6.6{slash}CB6{slash}A6-Pad3)") (class "Default")
      (node (ref "U2") (pin "3") (pinfunction "P6.6/CB6/A6_3") (pintype "passive"))
    )
    (net (code "81") (name "unconnected-(U2-P6.7{slash}CB7{slash}A7-Pad4)") (class "Default")
      (node (ref "U2") (pin "4") (pinfunction "P6.7/CB7/A7_4") (pintype "passive"))
    )
    (net (code "82") (name "unconnected-(U2-P7.0{slash}CB8{slash}A12-Pad5)") (class "Default")
      (node (ref "U2") (pin "5") (pinfunction "P7.0/CB8/A12_5") (pintype "passive"))
    )
    (net (code "83") (name "unconnected-(U2-P7.1{slash}CB9{slash}A13-Pad6)") (class "Default")
      (node (ref "U2") (pin "6") (pinfunction "P7.1/CB9/A13_6") (pintype "passive"))
    )
    (net (code "84") (name "unconnected-(U2-P7.2{slash}CB10{slash}A14-Pad7)") (class "Default")
      (node (ref "U2") (pin "7") (pinfunction "P7.2/CB10/A14_7") (pintype "passive"))
    )
    (net (code "85") (name "unconnected-(U2-P7.3{slash}CB11{slash}A15-Pad8)") (class "Default")
      (node (ref "U2") (pin "8") (pinfunction "P7.3/CB11/A15_8") (pintype "passive"))
    )
    (net (code "86") (name "unconnected-(U2-P7.4{slash}TB0.2-Pad57)") (class "Default")
      (node (ref "U2") (pin "57") (pinfunction "P7.4/TB0.2_57") (pintype "passive"))
    )
    (net (code "87") (name "unconnected-(U2-P7.5{slash}TB0.3-Pad58)") (class "Default")
      (node (ref "U2") (pin "58") (pinfunction "P7.5/TB0.3_58") (pintype "passive"))
    )
    (net (code "88") (name "unconnected-(U2-P7.6{slash}TB0.4-Pad59)") (class "Default")
      (node (ref "U2") (pin "59") (pinfunction "P7.6/TB0.4_59") (pintype "passive"))
    )
    (net (code "89") (name "unconnected-(U2-P7.7{slash}TB0CLK{slash}MCLK-Pad60)") (class "Default")
      (node (ref "U2") (pin "60") (pinfunction "P7.7/TB0CLK/MCLK_60") (pintype "passive"))
    )
    (net (code "90") (name "unconnected-(U2-P8.0-Pad15)") (class "Default")
      (node (ref "U2") (pin "15") (pinfunction "P8.0_15") (pintype "passive"))
    )
    (net (code "91") (name "unconnected-(U2-P8.1-Pad16)") (class "Default")
      (node (ref "U2") (pin "16") (pinfunction "P8.1_16") (pintype "passive"))
    )
    (net (code "92") (name "unconnected-(U2-P8.2-Pad17)") (class "Default")
      (node (ref "U2") (pin "17") (pinfunction "P8.2_17") (pintype "passive"))
    )
    (net (code "93") (name "unconnected-(U2-PJ.0{slash}TDO-Pad72)") (class "Default")
      (node (ref "U2") (pin "72") (pinfunction "PJ.0/TDO_72") (pintype "passive"))
    )
    (net (code "94") (name "unconnected-(U2-PJ.1{slash}TDI{slash}TCLK-Pad73)") (class "Default")
      (node (ref "U2") (pin "73") (pinfunction "PJ.1/TDI/TCLK_73") (pintype "passive"))
    )
    (net (code "95") (name "unconnected-(U2-PJ.2{slash}TMS-Pad74)") (class "Default")
      (node (ref "U2") (pin "74") (pinfunction "PJ.2/TMS_74") (pintype "passive"))
    )
    (net (code "96") (name "unconnected-(U2-PJ.3{slash}TCK-Pad75)") (class "Default")
      (node (ref "U2") (pin "75") (pinfunction "PJ.3/TCK_75") (pintype "passive"))
    )
    (net (code "97") (name "unconnected-(U5-I{slash}O1-Pad6)") (class "Default")
      (node (ref "U5") (pin "6") (pinfunction "I/O1_6") (pintype "passive"))
    )
    (net (code "98") (name "unconnected-(U5-I{slash}O2-Pad4)") (class "Default")
      (node (ref "U5") (pin "4") (pinfunction "I/O2_4") (pintype "passive"))
    )
  )
)
